# Nusbio_FT232H.net
KiCad netlist of a schematic drawn in EAGLE
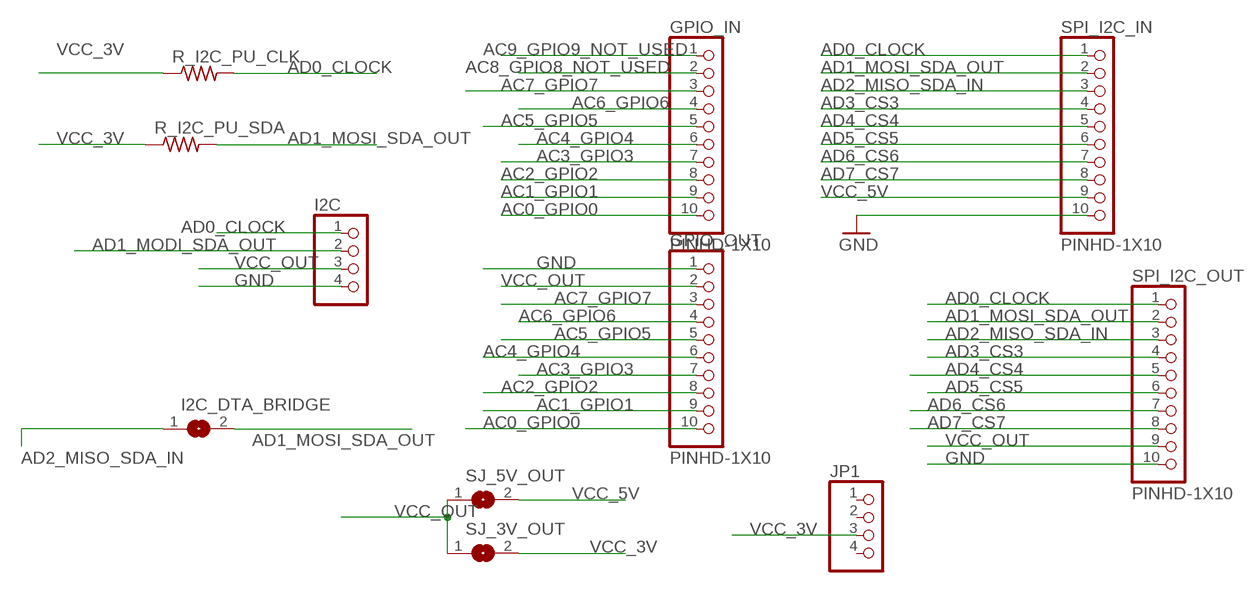
[diagram p0: schematic, sheet 1]

(export (version "E")
  (design (tool "Eeschema 10.0.6"))
  (components
    (comp (ref "GPIO_IN")
      (value "PINHD-1X10")
      (footprint "eagle-import:1X10-BIG")
      (libsource (lib "eagle-import") (part "PINHD-1X10"))
    )
    (comp (ref "GPIO_OUT")
      (value "PINHD-1X10")
      (footprint "eagle-import:1X10-BIG")
      (libsource (lib "eagle-import") (part "PINHD-1X10"))
    )
    (comp (ref "I2C")
      (value "PINHD-1X4")
      (footprint "eagle-import:1X04")
      (libsource (lib "eagle-import") (part "PINHD-1X4"))
    )
    (comp (ref "I2C_DTA_BRIDGE")
      (value "SOLDERJUMPERREFLOW")
      (footprint "eagle-import:SOLDERJUMPER_REFLOW")
      (libsource (lib "eagle-import") (part "SOLDERJUMPERREFLOW"))
    )
    (comp (ref "JP1")
      (value "PINHD-1X4")
      (footprint "eagle-import:1X04")
      (libsource (lib "eagle-import") (part "PINHD-1X4"))
    )
    (comp (ref "R_I2C_PU_CLK")
      (value "R-US_R1206")
      (footprint "eagle-import:R1206")
      (libsource (lib "eagle-import") (part "R-US_R1206"))
    )
    (comp (ref "R_I2C_PU_SDA")
      (value "R-US_R1206")
      (footprint "eagle-import:R1206")
      (libsource (lib "eagle-import") (part "R-US_R1206"))
    )
    (comp (ref "SJ_3V_OUT")
      (value "SOLDERJUMPERREFLOW")
      (footprint "eagle-import:SOLDERJUMPER_REFLOW")
      (libsource (lib "eagle-import") (part "SOLDERJUMPERREFLOW"))
    )
    (comp (ref "SJ_5V_OUT")
      (value "SOLDERJUMPERREFLOW")
      (footprint "eagle-import:SOLDERJUMPER_REFLOW")
      (libsource (lib "eagle-import") (part "SOLDERJUMPERREFLOW"))
    )
    (comp (ref "SPI_I2C_IN")
      (value "PINHD-1X10")
      (footprint "eagle-import:1X10-BIG")
      (libsource (lib "eagle-import") (part "PINHD-1X10"))
    )
    (comp (ref "SPI_I2C_OUT")
      (value "PINHD-1X10")
      (footprint "eagle-import:1X10-BIG")
      (libsource (lib "eagle-import") (part "PINHD-1X10"))
    )
  )
  (nets
    (net (code "1") (name "/AC0_GPIO0") (class "Default")
      (node (ref "GPIO_IN") (pin "10") (pinfunction "10_10") (pintype "passive"))
      (node (ref "GPIO_OUT") (pin "10") (pinfunction "10_10") (pintype "passive"))
    )
    (net (code "2") (name "/AC1_GPIO1") (class "Default")
      (node (ref "GPIO_IN") (pin "9") (pinfunction "9_9") (pintype "passive"))
      (node (ref "GPIO_OUT") (pin "9") (pinfunction "9_9") (pintype "passive"))
    )
    (net (code "3") (name "/AC2_GPIO2") (class "Default")
      (node (ref "GPIO_IN") (pin "8") (pinfunction "8_8") (pintype "passive"))
      (node (ref "GPIO_OUT") (pin "8") (pinfunction "8_8") (pintype "passive"))
    )
    (net (code "4") (name "/AC3_GPIO3") (class "Default")
      (node (ref "GPIO_IN") (pin "7") (pinfunction "7_7") (pintype "passive"))
      (node (ref "GPIO_OUT") (pin "7") (pinfunction "7_7") (pintype "passive"))
    )
    (net (code "5") (name "/AC4_GPIO4") (class "Default")
      (node (ref "GPIO_IN") (pin "6") (pinfunction "6_6") (pintype "passive"))
      (node (ref "GPIO_OUT") (pin "6") (pinfunction "6_6") (pintype "passive"))
    )
    (net (code "6") (name "/AC5_GPIO5") (class "Default")
      (node (ref "GPIO_IN") (pin "5") (pinfunction "5_5") (pintype "passive"))
      (node (ref "GPIO_OUT") (pin "5") (pinfunction "5_5") (pintype "passive"))
    )
    (net (code "7") (name "/AC6_GPIO6") (class "Default")
      (node (ref "GPIO_IN") (pin "4") (pinfunction "4_4") (pintype "passive"))
      (node (ref "GPIO_OUT") (pin "4") (pinfunction "4_4") (pintype "passive"))
    )
    (net (code "8") (name "/AC7_GPIO7") (class "Default")
      (node (ref "GPIO_IN") (pin "3") (pinfunction "3_3") (pintype "passive"))
      (node (ref "GPIO_OUT") (pin "3") (pinfunction "3_3") (pintype "passive"))
    )
    (net (code "9") (name "/AC8_GPIO8_NOT_USED") (class "Default")
      (node (ref "GPIO_IN") (pin "2") (pinfunction "2_2") (pintype "passive"))
    )
    (net (code "10") (name "/AC9_GPIO9_NOT_USED") (class "Default")
      (node (ref "GPIO_IN") (pin "1") (pinfunction "1_1") (pintype "passive"))
    )
    (net (code "11") (name "/AD0_CLOCK") (class "Default")
      (node (ref "I2C") (pin "1") (pinfunction "1_1") (pintype "passive"))
      (node (ref "R_I2C_PU_CLK") (pin "2") (pinfunction "2_2") (pintype "passive"))
      (node (ref "SPI_I2C_IN") (pin "1") (pinfunction "1_1") (pintype "passive"))
      (node (ref "SPI_I2C_OUT") (pin "1") (pinfunction "1_1") (pintype "passive"))
    )
    (net (code "12") (name "/AD1_MODI_SDA_OUT") (class "Default")
      (node (ref "I2C") (pin "2") (pinfunction "2_2") (pintype "passive"))
    )
    (net (code "13") (name "/AD1_MOSI_SDA_OUT") (class "Default")
      (node (ref "I2C_DTA_BRIDGE") (pin "2") (pinfunction "2_2") (pintype "passive"))
      (node (ref "R_I2C_PU_SDA") (pin "2") (pinfunction "2_2") (pintype "passive"))
      (node (ref "SPI_I2C_IN") (pin "2") (pinfunction "2_2") (pintype "passive"))
      (node (ref "SPI_I2C_OUT") (pin "2") (pinfunction "2_2") (pintype "passive"))
    )
    (net (code "14") (name "/AD2_MISO_SDA_IN") (class "Default")
      (node (ref "I2C_DTA_BRIDGE") (pin "1") (pinfunction "1_1") (pintype "passive"))
      (node (ref "SPI_I2C_IN") (pin "3") (pinfunction "3_3") (pintype "passive"))
      (node (ref "SPI_I2C_OUT") (pin "3") (pinfunction "3_3") (pintype "passive"))
    )
    (net (code "15") (name "/AD3_CS3") (class "Default")
      (node (ref "SPI_I2C_IN") (pin "4") (pinfunction "4_4") (pintype "passive"))
      (node (ref "SPI_I2C_OUT") (pin "4") (pinfunction "4_4") (pintype "passive"))
    )
    (net (code "16") (name "/AD4_CS4") (class "Default")
      (node (ref "SPI_I2C_IN") (pin "5") (pinfunction "5_5") (pintype "passive"))
      (node (ref "SPI_I2C_OUT") (pin "5") (pinfunction "5_5") (pintype "passive"))
    )
    (net (code "17") (name "/AD5_CS5") (class "Default")
      (node (ref "SPI_I2C_IN") (pin "6") (pinfunction "6_6") (pintype "passive"))
      (node (ref "SPI_I2C_OUT") (pin "6") (pinfunction "6_6") (pintype "passive"))
    )
    (net (code "18") (name "/AD6_CS6") (class "Default")
      (node (ref "SPI_I2C_IN") (pin "7") (pinfunction "7_7") (pintype "passive"))
      (node (ref "SPI_I2C_OUT") (pin "7") (pinfunction "7_7") (pintype "passive"))
    )
    (net (code "19") (name "/AD7_CS7") (class "Default")
      (node (ref "SPI_I2C_IN") (pin "8") (pinfunction "8_8") (pintype "passive"))
      (node (ref "SPI_I2C_OUT") (pin "8") (pinfunction "8_8") (pintype "passive"))
    )
    (net (code "20") (name "/VCC_3V") (class "Default")
      (node (ref "JP1") (pin "3") (pinfunction "3_3") (pintype "passive"))
      (node (ref "R_I2C_PU_CLK") (pin "1") (pinfunction "1_1") (pintype "passive"))
      (node (ref "R_I2C_PU_SDA") (pin "1") (pinfunction "1_1") (pintype "passive"))
      (node (ref "SJ_3V_OUT") (pin "2") (pinfunction "2_2") (pintype "passive"))
    )
    (net (code "21") (name "/VCC_5V") (class "Default")
      (node (ref "SJ_5V_OUT") (pin "2") (pinfunction "2_2") (pintype "passive"))
      (node (ref "SPI_I2C_IN") (pin "9") (pinfunction "9_9") (pintype "passive"))
    )
    (net (code "22") (name "/VCC_OUT") (class "Default")
      (node (ref "GPIO_OUT") (pin "2") (pinfunction "2_2") (pintype "passive"))
      (node (ref "I2C") (pin "3") (pinfunction "3_3") (pintype "passive"))
      (node (ref "SJ_3V_OUT") (pin "1") (pinfunction "1_1") (pintype "passive"))
      (node (ref "SJ_5V_OUT") (pin "1") (pinfunction "1_1") (pintype "passive"))
      (node (ref "SPI_I2C_OUT") (pin "9") (pinfunction "9_9") (pintype "passive"))
    )
    (net (code "23") (name "GND") (class "Default")
      (node (ref "GPIO_OUT") (pin "1") (pinfunction "1_1") (pintype "passive"))
      (node (ref "I2C") (pin "4") (pinfunction "4_4") (pintype "passive"))
      (node (ref "SPI_I2C_IN") (pin "10") (pinfunction "10_10") (pintype "passive"))
      (node (ref "SPI_I2C_OUT") (pin "10") (pinfunction "10_10") (pintype "passive"))
    )
    (net (code "24") (name "unconnected-(JP1-Pad1)") (class "Default")
      (node (ref "JP1") (pin "1") (pinfunction "1_1") (pintype "passive"))
    )
    (net (code "25") (name "unconnected-(JP1-Pad2)") (class "Default")
      (node (ref "JP1") (pin "2") (pinfunction "2_2") (pintype "passive"))
    )
    (net (code "26") (name "unconnected-(JP1-Pad4)") (class "Default")
      (node (ref "JP1") (pin "4") (pinfunction "4_4") (pintype "passive"))
    )
  )
)
